# 09_USB-DFU.net
KiCad netlist of a schematic drawn in Altium Designer
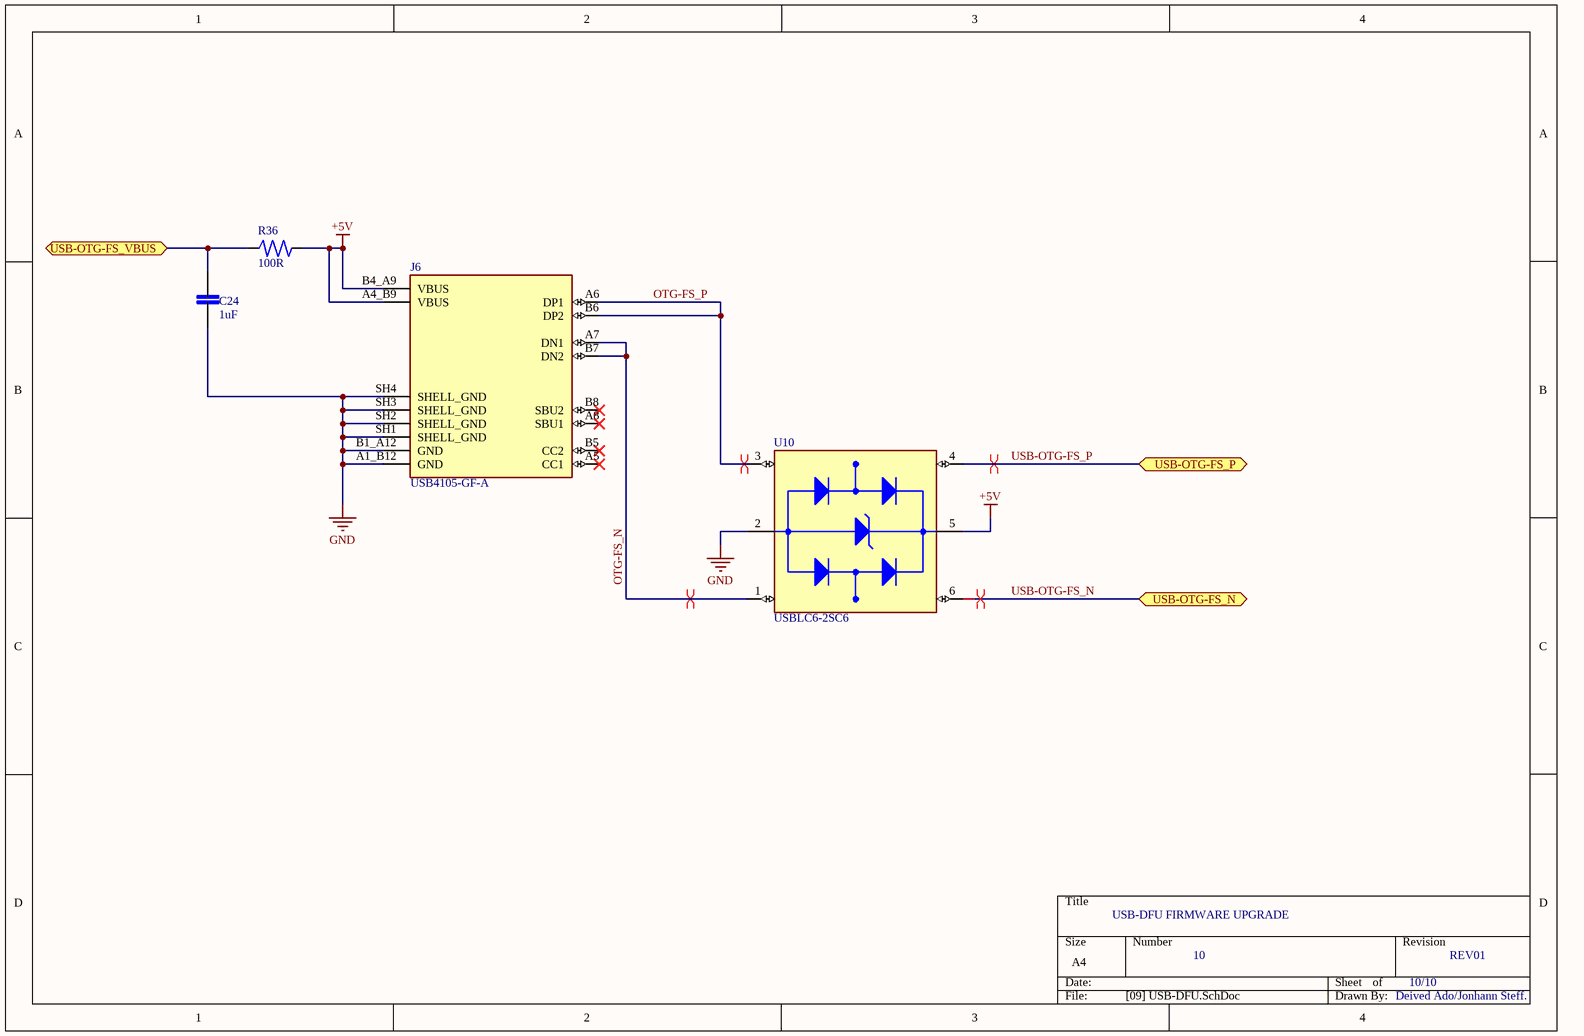
[diagram p0: [09] USB-DFU.SchDoc]

(export (version "E")
  (design (tool "Eeschema 10.0.6"))
  (components
    (comp (ref "C24")
      (value "1uF")
      (footprint "CAP_0603")
      (description "Generic capacitor symbol")
      (libsource (lib "Integrated_Library_IST") (part "C_Small"))
    )
    (comp (ref "J6")
      (value "USB4105-GF-A")
      (footprint "GCT_USB4105-GF-A")
      (fields (field (name "MF") "GCT"))
      (libsource (lib "Integrated_Library_IST") (part "USB4105-GF-A"))
    )
    (comp (ref "R36")
      (value "100R")
      (footprint "RES_0603")
      (description "Generic Resistor symbol")
      (libsource (lib "Integrated_Library_IST") (part "R_Small"))
    )
    (comp (ref "U10")
      (value "USBLC6-2SC6")
      (footprint "SOT95P280X145-6N")
      (description "17V Clamp 5A (8/20Âµs) Ipp Tvs Diode Surface Mount SOT-23-6")
      (fields (field (name "MF") "STMicroelectronics"))
      (libsource (lib "Integrated_Library - Rev1-DESKTOP-6DENAEC") (part "USBLC6-2SC6"))
    )
  )
  (nets
    (net (code "1") (name "+5V") (class "Default")
      (node (ref "J6") (pin "A4_B9") (pinfunction "VBUS_A4_B9") (pintype "power_in"))
      (node (ref "J6") (pin "B4_A9") (pinfunction "VBUS_B4_A9") (pintype "power_in"))
      (node (ref "R36") (pin "1") (pinfunction "1_1") (pintype "passive"))
      (node (ref "U10") (pin "5") (pinfunction "VBUS_5") (pintype "power_in"))
    )
    (net (code "2") (name "/OTG-FS_N") (class "Default")
      (node (ref "J6") (pin "A7") (pinfunction "DN1_A7") (pintype "bidirectional"))
      (node (ref "J6") (pin "B7") (pinfunction "DN2_B7") (pintype "bidirectional"))
      (node (ref "U10") (pin "1") (pinfunction "I/O1_IN_1") (pintype "bidirectional"))
    )
    (net (code "3") (name "/OTG-FS_P") (class "Default")
      (node (ref "J6") (pin "A6") (pinfunction "DP1_A6") (pintype "bidirectional"))
      (node (ref "J6") (pin "B6") (pinfunction "DP2_B6") (pintype "bidirectional"))
      (node (ref "U10") (pin "3") (pinfunction "I/O2_IN_3") (pintype "bidirectional"))
    )
    (net (code "4") (name "/USB-OTG-FS_N") (class "Default")
      (node (ref "U10") (pin "6") (pinfunction "I/O1_OUT_6") (pintype "bidirectional"))
    )
    (net (code "5") (name "/USB-OTG-FS_P") (class "Default")
      (node (ref "U10") (pin "4") (pinfunction "I/O2_OUT_4") (pintype "bidirectional"))
    )
    (net (code "6") (name "/USB-OTG-FS_VBUS") (class "Default")
      (node (ref "C24") (pin "2") (pinfunction "2_2") (pintype "passive"))
      (node (ref "R36") (pin "2") (pinfunction "2_2") (pintype "passive"))
    )
    (net (code "7") (name "GND") (class "Default")
      (node (ref "C24") (pin "1") (pinfunction "1_1") (pintype "passive"))
      (node (ref "J6") (pin "A1_B12") (pinfunction "GND_A1_B12") (pintype "power_in"))
      (node (ref "J6") (pin "B1_A12") (pinfunction "GND_B1_A12") (pintype "power_in"))
      (node (ref "J6") (pin "SH1") (pinfunction "SHELL_GND_SH1") (pintype "power_in"))
      (node (ref "J6") (pin "SH2") (pinfunction "SHELL_GND_SH2") (pintype "power_in"))
      (node (ref "J6") (pin "SH3") (pinfunction "SHELL_GND_SH3") (pintype "power_in"))
      (node (ref "J6") (pin "SH4") (pinfunction "SHELL_GND_SH4") (pintype "power_in"))
      (node (ref "U10") (pin "2") (pinfunction "GND_2") (pintype "power_in"))
    )
    (net (code "8") (name "unconnected-(J6-CC1-PadA5)") (class "Default")
      (node (ref "J6") (pin "A5") (pinfunction "CC1_A5") (pintype "bidirectional+no_connect"))
    )
    (net (code "9") (name "unconnected-(J6-CC2-PadB5)") (class "Default")
      (node (ref "J6") (pin "B5") (pinfunction "CC2_B5") (pintype "bidirectional+no_connect"))
    )
    (net (code "10") (name "unconnected-(J6-SBU1-PadA8)") (class "Default")
      (node (ref "J6") (pin "A8") (pinfunction "SBU1_A8") (pintype "bidirectional+no_connect"))
    )
    (net (code "11") (name "unconnected-(J6-SBU2-PadB8)") (class "Default")
      (node (ref "J6") (pin "B8") (pinfunction "SBU2_B8") (pintype "bidirectional+no_connect"))
    )
  )
)
